# R451E.net
KiCad netlist of a schematic drawn in EAGLE
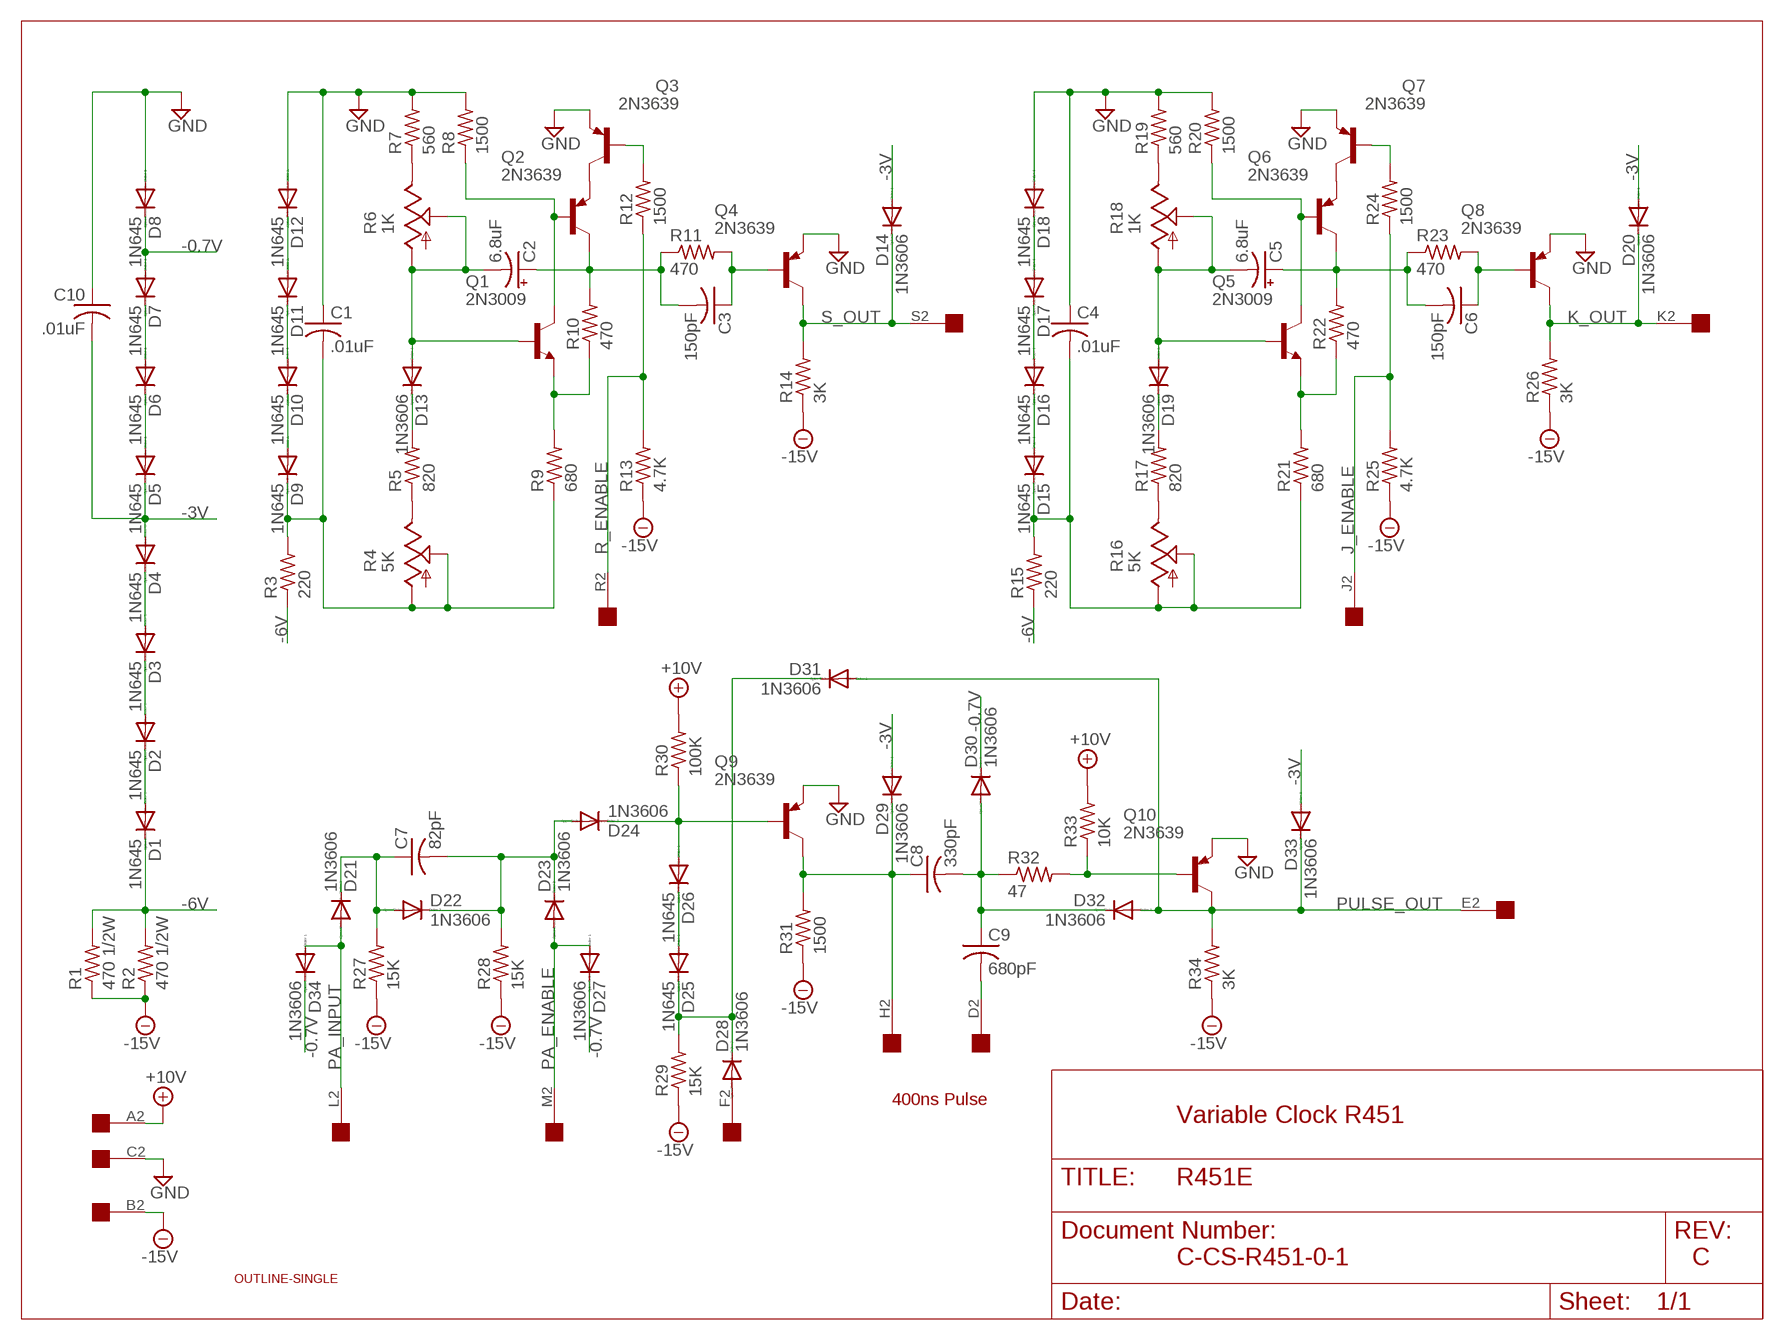
[diagram p0: schematic, sheet 1]

(export (version "E")
  (design (tool "Eeschema 10.0.6"))
  (components
    (comp (ref "C1")
      (value ".01uF")
      (footprint "eagle-import:C050-025X075")
      (libsource (lib "eagle-import") (part "C-US050-025X075"))
    )
    (comp (ref "C2")
      (value "6.8uF")
      (footprint "eagle-import:E12-4")
      (libsource (lib "eagle-import") (part "CPOL-USE12-4AXIAL"))
    )
    (comp (ref "C3")
      (value "150pF")
      (footprint "eagle-import:C075-032X103")
      (libsource (lib "eagle-import") (part "C-US075-032X103"))
    )
    (comp (ref "C4")
      (value ".01uF")
      (footprint "eagle-import:C050-025X075")
      (libsource (lib "eagle-import") (part "C-US050-025X075"))
    )
    (comp (ref "C5")
      (value "6.8uF")
      (footprint "eagle-import:E12-4")
      (libsource (lib "eagle-import") (part "CPOL-USE12-4AXIAL"))
    )
    (comp (ref "C6")
      (value "150pF")
      (footprint "eagle-import:C075-032X103")
      (libsource (lib "eagle-import") (part "C-US075-032X103"))
    )
    (comp (ref "C7")
      (value "82pF")
      (footprint "eagle-import:C075-032X103")
      (libsource (lib "eagle-import") (part "C-US075-032X103"))
    )
    (comp (ref "C8")
      (value "330pF")
      (footprint "eagle-import:C075-032X103")
      (libsource (lib "eagle-import") (part "C-US075-032X103"))
    )
    (comp (ref "C9")
      (value "680pF")
      (footprint "eagle-import:C075-032X103")
      (libsource (lib "eagle-import") (part "C-US075-032X103"))
    )
    (comp (ref "C10")
      (value ".01uF")
      (footprint "eagle-import:C050-025X075")
      (libsource (lib "eagle-import") (part "C-US050-025X075"))
    )
    (comp (ref "D1")
      (value "1N645")
      (footprint "eagle-import:DO35-10")
      (libsource (lib "eagle-import") (part "1N4148DO35-10"))
    )
    (comp (ref "D2")
      (value "1N645")
      (footprint "eagle-import:DO35-10")
      (libsource (lib "eagle-import") (part "1N4148DO35-10"))
    )
    (comp (ref "D3")
      (value "1N645")
      (footprint "eagle-import:DO35-10")
      (libsource (lib "eagle-import") (part "1N4148DO35-10"))
    )
    (comp (ref "D4")
      (value "1N645")
      (footprint "eagle-import:DO35-10")
      (libsource (lib "eagle-import") (part "1N4148DO35-10"))
    )
    (comp (ref "D5")
      (value "1N645")
      (footprint "eagle-import:DO35-10")
      (libsource (lib "eagle-import") (part "1N4148DO35-10"))
    )
    (comp (ref "D6")
      (value "1N645")
      (footprint "eagle-import:DO35-10")
      (libsource (lib "eagle-import") (part "1N4148DO35-10"))
    )
    (comp (ref "D7")
      (value "1N645")
      (footprint "eagle-import:DO35-10")
      (libsource (lib "eagle-import") (part "1N4148DO35-10"))
    )
    (comp (ref "D8")
      (value "1N645")
      (footprint "eagle-import:DO35-10")
      (libsource (lib "eagle-import") (part "1N4148DO35-10"))
    )
    (comp (ref "D9")
      (value "1N645")
      (footprint "eagle-import:DO35-10")
      (libsource (lib "eagle-import") (part "1N4148DO35-10"))
    )
    (comp (ref "D10")
      (value "1N645")
      (footprint "eagle-import:DO35-10")
      (libsource (lib "eagle-import") (part "1N4148DO35-10"))
    )
    (comp (ref "D11")
      (value "1N645")
      (footprint "eagle-import:DO35-10")
      (libsource (lib "eagle-import") (part "1N4148DO35-10"))
    )
    (comp (ref "D12")
      (value "1N645")
      (footprint "eagle-import:DO35-10")
      (libsource (lib "eagle-import") (part "1N4148DO35-10"))
    )
    (comp (ref "D13")
      (value "1N3606")
      (footprint "eagle-import:DO35-10")
      (libsource (lib "eagle-import") (part "1N4148DO35-10"))
    )
    (comp (ref "D14")
      (value "1N3606")
      (footprint "eagle-import:DO35-10")
      (libsource (lib "eagle-import") (part "1N4148DO35-10"))
    )
    (comp (ref "D15")
      (value "1N645")
      (footprint "eagle-import:DO35-10")
      (libsource (lib "eagle-import") (part "1N4148DO35-10"))
    )
    (comp (ref "D16")
      (value "1N645")
      (footprint "eagle-import:DO35-10")
      (libsource (lib "eagle-import") (part "1N4148DO35-10"))
    )
    (comp (ref "D17")
      (value "1N645")
      (footprint "eagle-import:DO35-10")
      (libsource (lib "eagle-import") (part "1N4148DO35-10"))
    )
    (comp (ref "D18")
      (value "1N645")
      (footprint "eagle-import:DO35-10")
      (libsource (lib "eagle-import") (part "1N4148DO35-10"))
    )
    (comp (ref "D19")
      (value "1N3606")
      (footprint "eagle-import:DO35-10")
      (libsource (lib "eagle-import") (part "1N4148DO35-10"))
    )
    (comp (ref "D20")
      (value "1N3606")
      (footprint "eagle-import:DO35-10")
      (libsource (lib "eagle-import") (part "1N4148DO35-10"))
    )
    (comp (ref "D21")
      (value "1N3606")
      (footprint "eagle-import:DO35-10")
      (libsource (lib "eagle-import") (part "1N4148DO35-10"))
    )
    (comp (ref "D22")
      (value "1N3606")
      (footprint "eagle-import:DO35-10")
      (libsource (lib "eagle-import") (part "1N4148DO35-10"))
    )
    (comp (ref "D23")
      (value "1N3606")
      (footprint "eagle-import:DO35-10")
      (libsource (lib "eagle-import") (part "1N4148DO35-10"))
    )
    (comp (ref "D24")
      (value "1N3606")
      (footprint "eagle-import:DO35-10")
      (libsource (lib "eagle-import") (part "1N4148DO35-10"))
    )
    (comp (ref "D25")
      (value "1N645")
      (footprint "eagle-import:DO35-10")
      (libsource (lib "eagle-import") (part "1N4148DO35-10"))
    )
    (comp (ref "D26")
      (value "1N645")
      (footprint "eagle-import:DO35-10")
      (libsource (lib "eagle-import") (part "1N4148DO35-10"))
    )
    (comp (ref "D27")
      (value "1N3606")
      (footprint "eagle-import:DO35-10")
      (libsource (lib "eagle-import") (part "1N4148DO35-10"))
    )
    (comp (ref "D28")
      (value "1N3606")
      (footprint "eagle-import:DO35-10")
      (libsource (lib "eagle-import") (part "1N4148DO35-10"))
    )
    (comp (ref "D29")
      (value "1N3606")
      (footprint "eagle-import:DO35-10")
      (libsource (lib "eagle-import") (part "1N4148DO35-10"))
    )
    (comp (ref "D30")
      (value "1N3606")
      (footprint "eagle-import:DO35-10")
      (libsource (lib "eagle-import") (part "1N4148DO35-10"))
    )
    (comp (ref "D31")
      (value "1N3606")
      (footprint "eagle-import:DO35-10")
      (libsource (lib "eagle-import") (part "1N4148DO35-10"))
    )
    (comp (ref "D32")
      (value "1N3606")
      (footprint "eagle-import:DO35-10")
      (libsource (lib "eagle-import") (part "1N4148DO35-10"))
    )
    (comp (ref "D33")
      (value "1N3606")
      (footprint "eagle-import:DO35-10")
      (libsource (lib "eagle-import") (part "1N4148DO35-10"))
    )
    (comp (ref "D34")
      (value "1N3606")
      (footprint "eagle-import:DO35-10")
      (libsource (lib "eagle-import") (part "1N4148DO35-10"))
    )
    (comp (ref "Q1")
      (value "2N3009")
      (footprint "eagle-import:TO5")
      (libsource (lib "eagle-import") (part "2N2102"))
    )
    (comp (ref "Q2")
      (value "2N3639")
      (footprint "eagle-import:TO39")
      (libsource (lib "eagle-import") (part "2N2904"))
    )
    (comp (ref "Q3")
      (value "2N3639")
      (footprint "eagle-import:TO39")
      (libsource (lib "eagle-import") (part "2N2904"))
    )
    (comp (ref "Q4")
      (value "2N3639")
      (footprint "eagle-import:TO39")
      (libsource (lib "eagle-import") (part "2N2904"))
    )
    (comp (ref "Q5")
      (value "2N3009")
      (footprint "eagle-import:TO5")
      (libsource (lib "eagle-import") (part "2N2102"))
    )
    (comp (ref "Q6")
      (value "2N3639")
      (footprint "eagle-import:TO39")
      (libsource (lib "eagle-import") (part "2N2904"))
    )
    (comp (ref "Q7")
      (value "2N3639")
      (footprint "eagle-import:TO39")
      (libsource (lib "eagle-import") (part "2N2904"))
    )
    (comp (ref "Q8")
      (value "2N3639")
      (footprint "eagle-import:TO39")
      (libsource (lib "eagle-import") (part "2N2904"))
    )
    (comp (ref "Q9")
      (value "2N3639")
      (footprint "eagle-import:TO39")
      (libsource (lib "eagle-import") (part "2N2904"))
    )
    (comp (ref "Q10")
      (value "2N3639")
      (footprint "eagle-import:TO39")
      (libsource (lib "eagle-import") (part "2N2904"))
    )
    (comp (ref "R1")
      (value "470 1/2W")
      (footprint "eagle-import:0411_15")
      (libsource (lib "eagle-import") (part "R-US_0411/15"))
    )
    (comp (ref "R2")
      (value "470 1/2W")
      (footprint "eagle-import:0411_15")
      (libsource (lib "eagle-import") (part "R-US_0411/15"))
    )
    (comp (ref "R3")
      (value "220")
      (footprint "eagle-import:0207_10")
      (libsource (lib "eagle-import") (part "R-US_0207/10"))
    )
    (comp (ref "R4")
      (value "5K")
      (footprint "eagle-import:CT6")
      (libsource (lib "eagle-import") (part "TRIM_US-CT6"))
    )
    (comp (ref "R5")
      (value "820")
      (footprint "eagle-import:0207_10")
      (libsource (lib "eagle-import") (part "R-US_0207/10"))
    )
    (comp (ref "R6")
      (value "1K")
      (footprint "eagle-import:CT6")
      (libsource (lib "eagle-import") (part "TRIM_US-CT6"))
    )
    (comp (ref "R7")
      (value "560")
      (footprint "eagle-import:0207_10")
      (libsource (lib "eagle-import") (part "R-US_0207/10"))
    )
    (comp (ref "R8")
      (value "1500")
      (footprint "eagle-import:0207_10")
      (libsource (lib "eagle-import") (part "R-US_0207/10"))
    )
    (comp (ref "R9")
      (value "680")
      (footprint "eagle-import:0207_10")
      (libsource (lib "eagle-import") (part "R-US_0207/10"))
    )
    (comp (ref "R10")
      (value "470")
      (footprint "eagle-import:0207_10")
      (libsource (lib "eagle-import") (part "R-US_0207/10"))
    )
    (comp (ref "R11")
      (value "470")
      (footprint "eagle-import:0207_10")
      (libsource (lib "eagle-import") (part "R-US_0207/10"))
    )
    (comp (ref "R12")
      (value "1500")
      (footprint "eagle-import:0207_10")
      (libsource (lib "eagle-import") (part "R-US_0207/10"))
    )
    (comp (ref "R13")
      (value "4.7K")
      (footprint "eagle-import:0207_10")
      (libsource (lib "eagle-import") (part "R-US_0207/10"))
    )
    (comp (ref "R14")
      (value "3K")
      (footprint "eagle-import:0207_10")
      (libsource (lib "eagle-import") (part "R-US_0207/10"))
    )
    (comp (ref "R15")
      (value "220")
      (footprint "eagle-import:0207_10")
      (libsource (lib "eagle-import") (part "R-US_0207/10"))
    )
    (comp (ref "R16")
      (value "5K")
      (footprint "eagle-import:CT6")
      (libsource (lib "eagle-import") (part "TRIM_US-CT6"))
    )
    (comp (ref "R17")
      (value "820")
      (footprint "eagle-import:0207_10")
      (libsource (lib "eagle-import") (part "R-US_0207/10"))
    )
    (comp (ref "R18")
      (value "1K")
      (footprint "eagle-import:CT6")
      (libsource (lib "eagle-import") (part "TRIM_US-CT6"))
    )
    (comp (ref "R19")
      (value "560")
      (footprint "eagle-import:0207_10")
      (libsource (lib "eagle-import") (part "R-US_0207/10"))
    )
    (comp (ref "R20")
      (value "1500")
      (footprint "eagle-import:0207_10")
      (libsource (lib "eagle-import") (part "R-US_0207/10"))
    )
    (comp (ref "R21")
      (value "680")
      (footprint "eagle-import:0207_10")
      (libsource (lib "eagle-import") (part "R-US_0207/10"))
    )
    (comp (ref "R22")
      (value "470")
      (footprint "eagle-import:0207_10")
      (libsource (lib "eagle-import") (part "R-US_0207/10"))
    )
    (comp (ref "R23")
      (value "470")
      (footprint "eagle-import:0207_10")
      (libsource (lib "eagle-import") (part "R-US_0207/10"))
    )
    (comp (ref "R24")
      (value "1500")
      (footprint "eagle-import:0207_10")
      (libsource (lib "eagle-import") (part "R-US_0207/10"))
    )
    (comp (ref "R25")
      (value "4.7K")
      (footprint "eagle-import:0207_10")
      (libsource (lib "eagle-import") (part "R-US_0207/10"))
    )
    (comp (ref "R26")
      (value "3K")
      (footprint "eagle-import:0207_10")
      (libsource (lib "eagle-import") (part "R-US_0207/10"))
    )
    (comp (ref "R27")
      (value "15K")
      (footprint "eagle-import:0207_10")
      (libsource (lib "eagle-import") (part "R-US_0207/10"))
    )
    (comp (ref "R28")
      (value "15K")
      (footprint "eagle-import:0207_10")
      (libsource (lib "eagle-import") (part "R-US_0207/10"))
    )
    (comp (ref "R29")
      (value "15K")
      (footprint "eagle-import:0207_10")
      (libsource (lib "eagle-import") (part "R-US_0207/10"))
    )
    (comp (ref "R30")
      (value "100K")
      (footprint "eagle-import:0207_10")
      (libsource (lib "eagle-import") (part "R-US_0207/10"))
    )
    (comp (ref "R31")
      (value "1500")
      (footprint "eagle-import:0207_10")
      (libsource (lib "eagle-import") (part "R-US_0207/10"))
    )
    (comp (ref "R32")
      (value "47")
      (footprint "eagle-import:0207_10")
      (libsource (lib "eagle-import") (part "R-US_0207/10"))
    )
    (comp (ref "R33")
      (value "10K")
      (footprint "eagle-import:0207_10")
      (libsource (lib "eagle-import") (part "R-US_0207/10"))
    )
    (comp (ref "R34")
      (value "3K")
      (footprint "eagle-import:0207_10")
      (libsource (lib "eagle-import") (part "R-US_0207/10"))
    )
    (comp (ref "U$1")
      (value "OUTLINE-SINGLE")
      (footprint "eagle-import:SINGLE")
      (libsource (lib "eagle-import") (part "OUTLINE-SINGLE"))
    )
    (comp (ref "U$2")
      (value "EDGE-1")
      (footprint "eagle-import:EDGE-CON1")
      (libsource (lib "eagle-import") (part "EDGE-1"))
    )
  )
  (nets
    (net (code "1") (name "+10V") (class "Default")
      (node (ref "R30") (pin "2") (pinfunction "2_2") (pintype "passive"))
      (node (ref "R33") (pin "2") (pinfunction "2_2") (pintype "passive"))
      (node (ref "U$2") (pin "A2") (pinfunction "1_A2") (pintype "bidirectional"))
    )
    (net (code "2") (name "-15V") (class "Default")
      (node (ref "R1") (pin "1") (pinfunction "1_1") (pintype "passive"))
      (node (ref "R13") (pin "1") (pinfunction "1_1") (pintype "passive"))
      (node (ref "R14") (pin "1") (pinfunction "1_1") (pintype "passive"))
      (node (ref "R2") (pin "1") (pinfunction "1_1") (pintype "passive"))
      (node (ref "R25") (pin "1") (pinfunction "1_1") (pintype "passive"))
      (node (ref "R26") (pin "1") (pinfunction "1_1") (pintype "passive"))
      (node (ref "R27") (pin "1") (pinfunction "1_1") (pintype "passive"))
      (node (ref "R28") (pin "1") (pinfunction "1_1") (pintype "passive"))
      (node (ref "R29") (pin "1") (pinfunction "1_1") (pintype "passive"))
      (node (ref "R31") (pin "1") (pinfunction "1_1") (pintype "passive"))
      (node (ref "R34") (pin "1") (pinfunction "1_1") (pintype "passive"))
      (node (ref "U$2") (pin "B2") (pinfunction "1_B2") (pintype "bidirectional"))
    )
    (net (code "3") (name "/-0.7V") (class "Default")
      (node (ref "D27") (pin "C") (pinfunction "C_C") (pintype "passive"))
      (node (ref "D30") (pin "C") (pinfunction "C_C") (pintype "passive"))
      (node (ref "D34") (pin "C") (pinfunction "C_C") (pintype "passive"))
      (node (ref "D7") (pin "A") (pinfunction "A_A") (pintype "passive"))
      (node (ref "D8") (pin "C") (pinfunction "C_C") (pintype "passive"))
    )
    (net (code "4") (name "/-3V") (class "Default")
      (node (ref "C10") (pin "2") (pinfunction "2_2") (pintype "passive"))
      (node (ref "D14") (pin "A") (pinfunction "A_A") (pintype "passive"))
      (node (ref "D20") (pin "A") (pinfunction "A_A") (pintype "passive"))
      (node (ref "D29") (pin "A") (pinfunction "A_A") (pintype "passive"))
      (node (ref "D33") (pin "A") (pinfunction "A_A") (pintype "passive"))
      (node (ref "D4") (pin "A") (pinfunction "A_A") (pintype "passive"))
      (node (ref "D5") (pin "C") (pinfunction "C_C") (pintype "passive"))
    )
    (net (code "5") (name "/-6V") (class "Default")
      (node (ref "D1") (pin "C") (pinfunction "C_C") (pintype "passive"))
      (node (ref "R1") (pin "2") (pinfunction "2_2") (pintype "passive"))
      (node (ref "R15") (pin "1") (pinfunction "1_1") (pintype "passive"))
      (node (ref "R2") (pin "2") (pinfunction "2_2") (pintype "passive"))
      (node (ref "R3") (pin "1") (pinfunction "1_1") (pintype "passive"))
    )
    (net (code "6") (name "/J_ENABLE") (class "Default")
      (node (ref "R24") (pin "1") (pinfunction "1_1") (pintype "passive"))
      (node (ref "R25") (pin "2") (pinfunction "2_2") (pintype "passive"))
      (node (ref "U$2") (pin "J2") (pinfunction "1_J2") (pintype "bidirectional"))
    )
    (net (code "7") (name "/K_OUT") (class "Default")
      (node (ref "D20") (pin "C") (pinfunction "C_C") (pintype "passive"))
      (node (ref "Q8") (pin "3") (pinfunction "C_3") (pintype "passive"))
      (node (ref "R26") (pin "2") (pinfunction "2_2") (pintype "passive"))
      (node (ref "U$2") (pin "K2") (pinfunction "1_K2") (pintype "bidirectional"))
    )
    (net (code "8") (name "/PA_ENABLE") (class "Default")
      (node (ref "D23") (pin "A") (pinfunction "A_A") (pintype "passive"))
      (node (ref "D27") (pin "A") (pinfunction "A_A") (pintype "passive"))
      (node (ref "U$2") (pin "M2") (pinfunction "1_M2") (pintype "bidirectional"))
    )
    (net (code "9") (name "/PA_INPUT") (class "Default")
      (node (ref "D21") (pin "A") (pinfunction "A_A") (pintype "passive"))
      (node (ref "D34") (pin "A") (pinfunction "A_A") (pintype "passive"))
      (node (ref "U$2") (pin "L2") (pinfunction "1_L2") (pintype "bidirectional"))
    )
    (net (code "10") (name "/PULSE_OUT") (class "Default")
      (node (ref "D31") (pin "A") (pinfunction "A_A") (pintype "passive"))
      (node (ref "D32") (pin "A") (pinfunction "A_A") (pintype "passive"))
      (node (ref "D33") (pin "C") (pinfunction "C_C") (pintype "passive"))
      (node (ref "Q10") (pin "3") (pinfunction "C_3") (pintype "passive"))
      (node (ref "R34") (pin "2") (pinfunction "2_2") (pintype "passive"))
      (node (ref "U$2") (pin "E2") (pinfunction "1_E2") (pintype "bidirectional"))
    )
    (net (code "11") (name "/R_ENABLE") (class "Default")
      (node (ref "R12") (pin "1") (pinfunction "1_1") (pintype "passive"))
      (node (ref "R13") (pin "2") (pinfunction "2_2") (pintype "passive"))
      (node (ref "U$2") (pin "R2") (pinfunction "1_R2") (pintype "bidirectional"))
    )
    (net (code "12") (name "/S_OUT") (class "Default")
      (node (ref "D14") (pin "C") (pinfunction "C_C") (pintype "passive"))
      (node (ref "Q4") (pin "3") (pinfunction "C_3") (pintype "passive"))
      (node (ref "R14") (pin "2") (pinfunction "2_2") (pintype "passive"))
      (node (ref "U$2") (pin "S2") (pinfunction "1_S2") (pintype "bidirectional"))
    )
    (net (code "13") (name "GND") (class "Default")
      (node (ref "C1") (pin "1") (pinfunction "1_1") (pintype "passive"))
      (node (ref "C10") (pin "1") (pinfunction "1_1") (pintype "passive"))
      (node (ref "C4") (pin "1") (pinfunction "1_1") (pintype "passive"))
      (node (ref "D12") (pin "A") (pinfunction "A_A") (pintype "passive"))
      (node (ref "D18") (pin "A") (pinfunction "A_A") (pintype "passive"))
      (node (ref "D8") (pin "A") (pinfunction "A_A") (pintype "passive"))
      (node (ref "Q10") (pin "1") (pinfunction "E_1") (pintype "passive"))
      (node (ref "Q3") (pin "1") (pinfunction "E_1") (pintype "passive"))
      (node (ref "Q4") (pin "1") (pinfunction "E_1") (pintype "passive"))
      (node (ref "Q7") (pin "1") (pinfunction "E_1") (pintype "passive"))
      (node (ref "Q8") (pin "1") (pinfunction "E_1") (pintype "passive"))
      (node (ref "Q9") (pin "1") (pinfunction "E_1") (pintype "passive"))
      (node (ref "R19") (pin "2") (pinfunction "2_2") (pintype "passive"))
      (node (ref "R20") (pin "2") (pinfunction "2_2") (pintype "passive"))
      (node (ref "R7") (pin "2") (pinfunction "2_2") (pintype "passive"))
      (node (ref "R8") (pin "2") (pinfunction "2_2") (pintype "passive"))
      (node (ref "U$2") (pin "C2") (pinfunction "1_C2") (pintype "bidirectional"))
    )
    (net (code "14") (name "Net-(C1-Pad2)") (class "Default")
      (node (ref "C1") (pin "2") (pinfunction "2_2") (pintype "passive"))
      (node (ref "D9") (pin "C") (pinfunction "C_C") (pintype "passive"))
      (node (ref "R3") (pin "2") (pinfunction "2_2") (pintype "passive"))
      (node (ref "R4") (pin "A") (pinfunction "A_A") (pintype "passive"))
      (node (ref "R4") (pin "S") (pinfunction "S_S") (pintype "passive"))
      (node (ref "R9") (pin "1") (pinfunction "1_1") (pintype "passive"))
    )
    (net (code "15") (name "Net-(C4-Pad2)") (class "Default")
      (node (ref "C4") (pin "2") (pinfunction "2_2") (pintype "passive"))
      (node (ref "D15") (pin "C") (pinfunction "C_C") (pintype "passive"))
      (node (ref "R15") (pin "2") (pinfunction "2_2") (pintype "passive"))
      (node (ref "R16") (pin "A") (pinfunction "A_A") (pintype "passive"))
      (node (ref "R16") (pin "S") (pinfunction "S_S") (pintype "passive"))
      (node (ref "R21") (pin "1") (pinfunction "1_1") (pintype "passive"))
    )
    (net (code "16") (name "Net-(C7-Pad1)") (class "Default")
      (node (ref "C7") (pin "1") (pinfunction "1_1") (pintype "passive"))
      (node (ref "D21") (pin "C") (pinfunction "C_C") (pintype "passive"))
      (node (ref "D22") (pin "A") (pinfunction "A_A") (pintype "passive"))
      (node (ref "R27") (pin "2") (pinfunction "2_2") (pintype "passive"))
    )
    (net (code "17") (name "Net-(C7-Pad2)") (class "Default")
      (node (ref "C7") (pin "2") (pinfunction "2_2") (pintype "passive"))
      (node (ref "D22") (pin "C") (pinfunction "C_C") (pintype "passive"))
      (node (ref "D23") (pin "C") (pinfunction "C_C") (pintype "passive"))
      (node (ref "D24") (pin "A") (pinfunction "A_A") (pintype "passive"))
      (node (ref "R28") (pin "2") (pinfunction "2_2") (pintype "passive"))
    )
    (net (code "18") (name "Net-(C8-Pad2)") (class "Default")
      (node (ref "C8") (pin "2") (pinfunction "2_2") (pintype "passive"))
      (node (ref "C9") (pin "1") (pinfunction "1_1") (pintype "passive"))
      (node (ref "D30") (pin "A") (pinfunction "A_A") (pintype "passive"))
      (node (ref "D32") (pin "C") (pinfunction "C_C") (pintype "passive"))
      (node (ref "R32") (pin "1") (pinfunction "1_1") (pintype "passive"))
    )
    (net (code "19") (name "Net-(D1-PadA)") (class "Default")
      (node (ref "D1") (pin "A") (pinfunction "A_A") (pintype "passive"))
      (node (ref "D2") (pin "C") (pinfunction "C_C") (pintype "passive"))
    )
    (net (code "20") (name "Net-(D2-PadA)") (class "Default")
      (node (ref "D2") (pin "A") (pinfunction "A_A") (pintype "passive"))
      (node (ref "D3") (pin "C") (pinfunction "C_C") (pintype "passive"))
    )
    (net (code "21") (name "Net-(D3-PadA)") (class "Default")
      (node (ref "D3") (pin "A") (pinfunction "A_A") (pintype "passive"))
      (node (ref "D4") (pin "C") (pinfunction "C_C") (pintype "passive"))
    )
    (net (code "22") (name "Net-(D5-PadA)") (class "Default")
      (node (ref "D5") (pin "A") (pinfunction "A_A") (pintype "passive"))
      (node (ref "D6") (pin "C") (pinfunction "C_C") (pintype "passive"))
    )
    (net (code "23") (name "Net-(D6-PadA)") (class "Default")
      (node (ref "D6") (pin "A") (pinfunction "A_A") (pintype "passive"))
      (node (ref "D7") (pin "C") (pinfunction "C_C") (pintype "passive"))
    )
    (net (code "24") (name "Net-(D10-PadA)") (class "Default")
      (node (ref "D10") (pin "A") (pinfunction "A_A") (pintype "passive"))
      (node (ref "D11") (pin "C") (pinfunction "C_C") (pintype "passive"))
    )
    (net (code "25") (name "Net-(D10-PadC)") (class "Default")
      (node (ref "D10") (pin "C") (pinfunction "C_C") (pintype "passive"))
      (node (ref "D9") (pin "A") (pinfunction "A_A") (pintype "passive"))
    )
    (net (code "26") (name "Net-(D11-PadA)") (class "Default")
      (node (ref "D11") (pin "A") (pinfunction "A_A") (pintype "passive"))
      (node (ref "D12") (pin "C") (pinfunction "C_C") (pintype "passive"))
    )
    (net (code "27") (name "Net-(D13-PadC)") (class "Default")
      (node (ref "D13") (pin "C") (pinfunction "C_C") (pintype "passive"))
      (node (ref "R5") (pin "2") (pinfunction "2_2") (pintype "passive"))
    )
    (net (code "28") (name "Net-(D15-PadA)") (class "Default")
      (node (ref "D15") (pin "A") (pinfunction "A_A") (pintype "passive"))
      (node (ref "D16") (pin "C") (pinfunction "C_C") (pintype "passive"))
    )
    (net (code "29") (name "Net-(D16-PadA)") (class "Default")
      (node (ref "D16") (pin "A") (pinfunction "A_A") (pintype "passive"))
      (node (ref "D17") (pin "C") (pinfunction "C_C") (pintype "passive"))
    )
    (net (code "30") (name "Net-(D17-PadA)") (class "Default")
      (node (ref "D17") (pin "A") (pinfunction "A_A") (pintype "passive"))
      (node (ref "D18") (pin "C") (pinfunction "C_C") (pintype "passive"))
    )
    (net (code "31") (name "Net-(D19-PadC)") (class "Default")
      (node (ref "D19") (pin "C") (pinfunction "C_C") (pintype "passive"))
      (node (ref "R17") (pin "2") (pinfunction "2_2") (pintype "passive"))
    )
    (net (code "32") (name "Net-(D25-PadA)") (class "Default")
      (node (ref "D25") (pin "A") (pinfunction "A_A") (pintype "passive"))
      (node (ref "D26") (pin "C") (pinfunction "C_C") (pintype "passive"))
    )
    (net (code "33") (name "Net-(D25-PadC)") (class "Default")
      (node (ref "D25") (pin "C") (pinfunction "C_C") (pintype "passive"))
      (node (ref "D28") (pin "C") (pinfunction "C_C") (pintype "passive"))
      (node (ref "D31") (pin "C") (pinfunction "C_C") (pintype "passive"))
      (node (ref "R29") (pin "2") (pinfunction "2_2") (pintype "passive"))
    )
    (net (code "34") (name "Net-(Q1-B)") (class "Default")
      (node (ref "C2") (pin "-") (pinfunction "-_-") (pintype "passive"))
      (node (ref "D13") (pin "A") (pinfunction "A_A") (pintype "passive"))
      (node (ref "Q1") (pin "2") (pinfunction "B_2") (pintype "passive"))
      (node (ref "R6") (pin "A") (pinfunction "A_A") (pintype "passive"))
      (node (ref "R6") (pin "S") (pinfunction "S_S") (pintype "passive"))
    )
    (net (code "35") (name "Net-(Q1-C)") (class "Default")
      (node (ref "Q1") (pin "3") (pinfunction "C_3") (pintype "passive"))
      (node (ref "Q2") (pin "2") (pinfunction "B_2") (pintype "passive"))
      (node (ref "R8") (pin "1") (pinfunction "1_1") (pintype "passive"))
    )
    (net (code "36") (name "Net-(Q1-E)") (class "Default")
      (node (ref "Q1") (pin "1") (pinfunction "E_1") (pintype "passive"))
      (node (ref "R10") (pin "1") (pinfunction "1_1") (pintype "passive"))
      (node (ref "R9") (pin "2") (pinfunction "2_2") (pintype "passive"))
    )
    (net (code "37") (name "Net-(Q2-C)") (class "Default")
      (node (ref "C2") (pin "+") (pinfunction "+_+") (pintype "passive"))
      (node (ref "C3") (pin "2") (pinfunction "2_2") (pintype "passive"))
      (node (ref "Q2") (pin "3") (pinfunction "C_3") (pintype "passive"))
      (node (ref "R10") (pin "2") (pinfunction "2_2") (pintype "passive"))
      (node (ref "R11") (pin "1") (pinfunction "1_1") (pintype "passive"))
    )
    (net (code "38") (name "Net-(Q2-E)") (class "Default")
      (node (ref "Q2") (pin "1") (pinfunction "E_1") (pintype "passive"))
      (node (ref "Q3") (pin "3") (pinfunction "C_3") (pintype "passive"))
    )
    (net (code "39") (name "Net-(Q3-B)") (class "Default")
      (node (ref "Q3") (pin "2") (pinfunction "B_2") (pintype "passive"))
      (node (ref "R12") (pin "2") (pinfunction "2_2") (pintype "passive"))
    )
    (net (code "40") (name "Net-(Q4-B)") (class "Default")
      (node (ref "C3") (pin "1") (pinfunction "1_1") (pintype "passive"))
      (node (ref "Q4") (pin "2") (pinfunction "B_2") (pintype "passive"))
      (node (ref "R11") (pin "2") (pinfunction "2_2") (pintype "passive"))
    )
    (net (code "41") (name "Net-(Q5-B)") (class "Default")
      (node (ref "C5") (pin "-") (pinfunction "-_-") (pintype "passive"))
      (node (ref "D19") (pin "A") (pinfunction "A_A") (pintype "passive"))
      (node (ref "Q5") (pin "2") (pinfunction "B_2") (pintype "passive"))
      (node (ref "R18") (pin "A") (pinfunction "A_A") (pintype "passive"))
      (node (ref "R18") (pin "S") (pinfunction "S_S") (pintype "passive"))
    )
    (net (code "42") (name "Net-(Q5-C)") (class "Default")
      (node (ref "Q5") (pin "3") (pinfunction "C_3") (pintype "passive"))
      (node (ref "Q6") (pin "2") (pinfunction "B_2") (pintype "passive"))
      (node (ref "R20") (pin "1") (pinfunction "1_1") (pintype "passive"))
    )
    (net (code "43") (name "Net-(Q5-E)") (class "Default")
      (node (ref "Q5") (pin "1") (pinfunction "E_1") (pintype "passive"))
      (node (ref "R21") (pin "2") (pinfunction "2_2") (pintype "passive"))
      (node (ref "R22") (pin "1") (pinfunction "1_1") (pintype "passive"))
    )
    (net (code "44") (name "Net-(Q6-C)") (class "Default")
      (node (ref "C5") (pin "+") (pinfunction "+_+") (pintype "passive"))
      (node (ref "C6") (pin "2") (pinfunction "2_2") (pintype "passive"))
      (node (ref "Q6") (pin "3") (pinfunction "C_3") (pintype "passive"))
      (node (ref "R22") (pin "2") (pinfunction "2_2") (pintype "passive"))
      (node (ref "R23") (pin "1") (pinfunction "1_1") (pintype "passive"))
    )
    (net (code "45") (name "Net-(Q6-E)") (class "Default")
      (node (ref "Q6") (pin "1") (pinfunction "E_1") (pintype "passive"))
      (node (ref "Q7") (pin "3") (pinfunction "C_3") (pintype "passive"))
    )
    (net (code "46") (name "Net-(Q7-B)") (class "Default")
      (node (ref "Q7") (pin "2") (pinfunction "B_2") (pintype "passive"))
      (node (ref "R24") (pin "2") (pinfunction "2_2") (pintype "passive"))
    )
    (net (code "47") (name "Net-(Q8-B)") (class "Default")
      (node (ref "C6") (pin "1") (pinfunction "1_1") (pintype "passive"))
      (node (ref "Q8") (pin "2") (pinfunction "B_2") (pintype "passive"))
      (node (ref "R23") (pin "2") (pinfunction "2_2") (pintype "passive"))
    )
    (net (code "48") (name "Net-(Q9-B)") (class "Default")
      (node (ref "D24") (pin "C") (pinfunction "C_C") (pintype "passive"))
      (node (ref "D26") (pin "A") (pinfunction "A_A") (pintype "passive"))
      (node (ref "Q9") (pin "2") (pinfunction "B_2") (pintype "passive"))
      (node (ref "R30") (pin "1") (pinfunction "1_1") (pintype "passive"))
    )
    (net (code "49") (name "Net-(Q9-C)") (class "Default")
      (node (ref "C8") (pin "1") (pinfunction "1_1") (pintype "passive"))
      (node (ref "D29") (pin "C") (pinfunction "C_C") (pintype "passive"))
      (node (ref "Q9") (pin "3") (pinfunction "C_3") (pintype "passive"))
      (node (ref "R31") (pin "2") (pinfunction "2_2") (pintype "passive"))
      (node (ref "U$2") (pin "H2") (pinfunction "1_H2") (pintype "bidirectional"))
    )
    (net (code "50") (name "Net-(Q10-B)") (class "Default")
      (node (ref "Q10") (pin "2") (pinfunction "B_2") (pintype "passive"))
      (node (ref "R32") (pin "2") (pinfunction "2_2") (pintype "passive"))
      (node (ref "R33") (pin "1") (pinfunction "1_1") (pintype "passive"))
    )
    (net (code "51") (name "Net-(R4-PadE)") (class "Default")
      (node (ref "R4") (pin "E") (pinfunction "E_E") (pintype "passive"))
      (node (ref "R5") (pin "1") (pinfunction "1_1") (pintype "passive"))
    )
    (net (code "52") (name "Net-(R6-PadE)") (class "Default")
      (node (ref "R6") (pin "E") (pinfunction "E_E") (pintype "passive"))
      (node (ref "R7") (pin "1") (pinfunction "1_1") (pintype "passive"))
    )
    (net (code "53") (name "Net-(R16-PadE)") (class "Default")
      (node (ref "R16") (pin "E") (pinfunction "E_E") (pintype "passive"))
      (node (ref "R17") (pin "1") (pinfunction "1_1") (pintype "passive"))
    )
    (net (code "54") (name "Net-(R18-PadE)") (class "Default")
      (node (ref "R18") (pin "E") (pinfunction "E_E") (pintype "passive"))
      (node (ref "R19") (pin "1") (pinfunction "1_1") (pintype "passive"))
    )
    (net (code "55") (name "Net-(U$2D-1)") (class "Default")
      (node (ref "C9") (pin "2") (pinfunction "2_2") (pintype "passive"))
      (node (ref "U$2") (pin "D2") (pinfunction "1_D2") (pintype "bidirectional"))
    )
    (net (code "56") (name "Net-(U$2F-1)") (class "Default")
      (node (ref "D28") (pin "A") (pinfunction "A_A") (pintype "passive"))
      (node (ref "U$2") (pin "F2") (pinfunction "1_F2") (pintype "bidirectional"))
    )
  )
)
